# top.net
KiCad netlist of a schematic drawn in Altium Designer
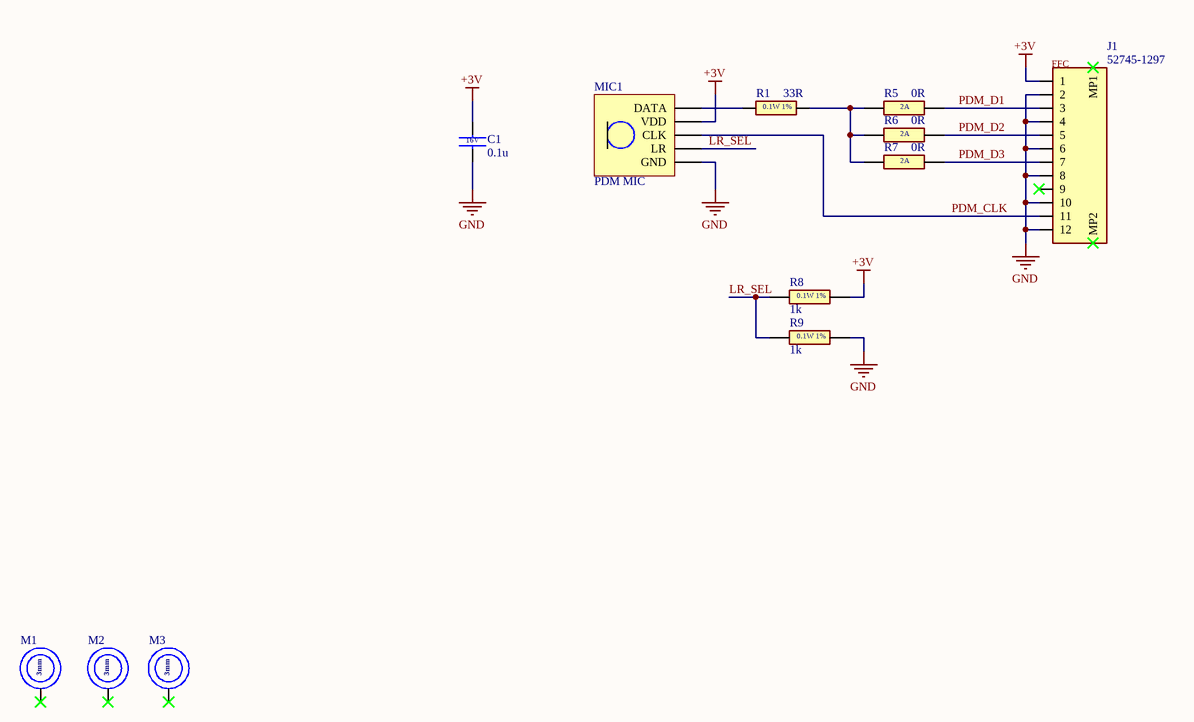
[diagram p0: top.SchDoc]

(export (version "E")
  (design (tool "Eeschema 10.0.6"))
  (components
    (comp (ref "C1")
      (value "0.1u")
      (footprint "CAPC1608X95N")
      (description "16V 0.1uF XR7 0603 10%")
      (fields
        (field (name "MANUFACTURER_PART_NUMBER") "C0603C104K4RAC-TU")
        (field (name "MOUSER PART NUMBER") "80-C0603C104K4RAC")
      )
      (libsource (lib "bch-lib") (part "ECK+100n16V"))
    )
    (comp (ref "J1")
      (value "52745-1297")
      (footprint "527451297")
      (fields (field (name "MOUSER PART NUMBER") "538-52745-1297"))
      (libsource (lib "bch-lib") (part "EJ+52745-1297"))
    )
    (comp (ref "M1")
      (value "MTH-3MM")
      (footprint "MountingHole_3.0mm_NPTH")
      (libsource (lib "bch-lib") (part "EMECH-MTH-3MM"))
    )
    (comp (ref "M2")
      (value "MTH-3MM")
      (footprint "MountingHole_3.0mm_NPTH")
      (libsource (lib "bch-lib") (part "EMECH-MTH-3MM"))
    )
    (comp (ref "M3")
      (value "MTH-3MM")
      (footprint "MountingHole_3.0mm_NPTH")
      (libsource (lib "bch-lib") (part "EMECH-MTH-3MM"))
    )
    (comp (ref "MIC1")
      (value "PDM MIC")
      (footprint "LLGA-5-4X3")
      (description "MEMS Microphones MIC DBP DIGITAL")
      (libsource (lib "bch-lib") (part "EX+IM67D130AXTSA2"))
    )
    (comp (ref "R1")
      (value "33R")
      (footprint "RESC1608X55N")
      (description "Resistor 1% 0.1W")
      (fields
        (field (name "MANUFACTURER_PART_NUMBER") "0603WAF330JT5E")
        (field (name "MOUSER PART NUMBER") "303-0603WAF330JT5E")
      )
      (libsource (lib "bch-lib") (part "ER+33R"))
    )
    (comp (ref "R5")
      (value "0R")
      (footprint "RESC1608X50N")
      (description "2A")
      (fields
        (field (name "MANUFACTURER_PART_NUMBER") "RCA06030000ZSEA")
        (field (name "MOUSER PART NUMBER") "71-RCA06030000ZSEA")
      )
      (libsource (lib "bch-lib") (part "ER+0R"))
    )
    (comp (ref "R6")
      (value "0R")
      (footprint "RESC1608X50N")
      (description "2A")
      (fields
        (field (name "MANUFACTURER_PART_NUMBER") "RCA06030000ZSEA")
        (field (name "MOUSER PART NUMBER") "71-RCA06030000ZSEA")
      )
      (libsource (lib "bch-lib") (part "ER+0R"))
    )
    (comp (ref "R7")
      (value "0R")
      (footprint "RESC1608X50N")
      (description "2A")
      (fields
        (field (name "MANUFACTURER_PART_NUMBER") "RCA06030000ZSEA")
        (field (name "MOUSER PART NUMBER") "71-RCA06030000ZSEA")
      )
      (libsource (lib "bch-lib") (part "ER+0R"))
    )
    (comp (ref "R8")
      (value "1k")
      (footprint "RESC1608X50N")
      (description "Resistor 1%, 0.1W")
      (fields
        (field (name "MANUFACTURER_PART_NUMBER") "CRCW06031K00FKEA")
        (field (name "MOUSER PART NUMBER") "71-CRCW0603-1.0K-E3")
      )
      (libsource (lib "bch-lib") (part "ER+1K"))
    )
    (comp (ref "R9")
      (value "1k")
      (footprint "RESC1608X50N")
      (description "Resistor 1%, 0.1W")
      (fields
        (field (name "MANUFACTURER_PART_NUMBER") "CRCW06031K00FKEA")
        (field (name "MOUSER PART NUMBER") "71-CRCW0603-1.0K-E3")
      )
      (libsource (lib "bch-lib") (part "ER+1K"))
    )
  )
  (nets
    (net (code "1") (name "+3V") (class "Default")
      (node (ref "C1") (pin "1") (pinfunction "1_1") (pintype "passive"))
      (node (ref "J1") (pin "1") (pinfunction "1_1") (pintype "passive"))
      (node (ref "MIC1") (pin "2") (pinfunction "VDD_2") (pintype "passive"))
      (node (ref "R8") (pin "2") (pinfunction "2_2") (pintype "passive"))
    )
    (net (code "2") (name "/LR_SEL") (class "Default")
      (node (ref "MIC1") (pin "4") (pinfunction "LR_4") (pintype "passive"))
      (node (ref "R8") (pin "1") (pinfunction "1_1") (pintype "passive"))
      (node (ref "R9") (pin "1") (pinfunction "1_1") (pintype "passive"))
    )
    (net (code "3") (name "/PDM_CLK") (class "Default")
      (node (ref "J1") (pin "11") (pinfunction "11_11") (pintype "passive"))
      (node (ref "MIC1") (pin "3") (pinfunction "CLK_3") (pintype "passive"))
    )
    (net (code "4") (name "/PDM_D1") (class "Default")
      (node (ref "J1") (pin "3") (pinfunction "3_3") (pintype "passive"))
      (node (ref "R5") (pin "2") (pinfunction "2_2") (pintype "passive"))
    )
    (net (code "5") (name "/PDM_D2") (class "Default")
      (node (ref "J1") (pin "5") (pinfunction "5_5") (pintype "passive"))
      (node (ref "R6") (pin "2") (pinfunction "2_2") (pintype "passive"))
    )
    (net (code "6") (name "/PDM_D3") (class "Default")
      (node (ref "J1") (pin "7") (pinfunction "7_7") (pintype "passive"))
      (node (ref "R7") (pin "2") (pinfunction "2_2") (pintype "passive"))
    )
    (net (code "7") (name "GND") (class "Default")
      (node (ref "C1") (pin "2") (pinfunction "2_2") (pintype "passive"))
      (node (ref "J1") (pin "10") (pinfunction "10_10") (pintype "passive"))
      (node (ref "J1") (pin "12") (pinfunction "12_12") (pintype "passive"))
      (node (ref "J1") (pin "2") (pinfunction "2_2") (pintype "passive"))
      (node (ref "J1") (pin "4") (pinfunction "4_4") (pintype "passive"))
      (node (ref "J1") (pin "6") (pinfunction "6_6") (pintype "passive"))
      (node (ref "J1") (pin "8") (pinfunction "8_8") (pintype "passive"))
      (node (ref "MIC1") (pin "5") (pinfunction "GND_5") (pintype "passive"))
      (node (ref "R9") (pin "2") (pinfunction "2_2") (pintype "passive"))
    )
    (net (code "8") (name "Net-(MIC1-DATA)") (class "Default")
      (node (ref "MIC1") (pin "1") (pinfunction "DATA_1") (pintype "passive"))
      (node (ref "R1") (pin "1") (pinfunction "1_1") (pintype "passive"))
    )
    (net (code "9") (name "Net-(R1-Pad2)") (class "Default")
      (node (ref "R1") (pin "2") (pinfunction "2_2") (pintype "passive"))
      (node (ref "R5") (pin "1") (pinfunction "1_1") (pintype "passive"))
      (node (ref "R6") (pin "1") (pinfunction "1_1") (pintype "passive"))
      (node (ref "R7") (pin "1") (pinfunction "1_1") (pintype "passive"))
    )
    (net (code "10") (name "unconnected-(J1-Pad9)") (class "Default")
      (node (ref "J1") (pin "9") (pinfunction "9_9") (pintype "passive+no_connect"))
    )
    (net (code "11") (name "unconnected-(J1-PadMP1)") (class "Default")
      (node (ref "J1") (pin "MP1") (pinfunction "MP1_MP1") (pintype "passive+no_connect"))
    )
    (net (code "12") (name "unconnected-(J1-PadMP2)") (class "Default")
      (node (ref "J1") (pin "MP2") (pinfunction "MP2_MP2") (pintype "passive+no_connect"))
    )
    (net (code "13") (name "unconnected-(M1-Pad1)") (class "Default")
      (node (ref "M1") (pin "1") (pinfunction "1_1") (pintype "passive+no_connect"))
    )
    (net (code "14") (name "unconnected-(M2-Pad1)") (class "Default")
      (node (ref "M2") (pin "1") (pinfunction "1_1") (pintype "passive+no_connect"))
    )
    (net (code "15") (name "unconnected-(M3-Pad1)") (class "Default")
      (node (ref "M3") (pin "1") (pinfunction "1_1") (pintype "passive+no_connect"))
    )
  )
)
